# buffer.net
KiCad netlist of a schematic drawn in EAGLE
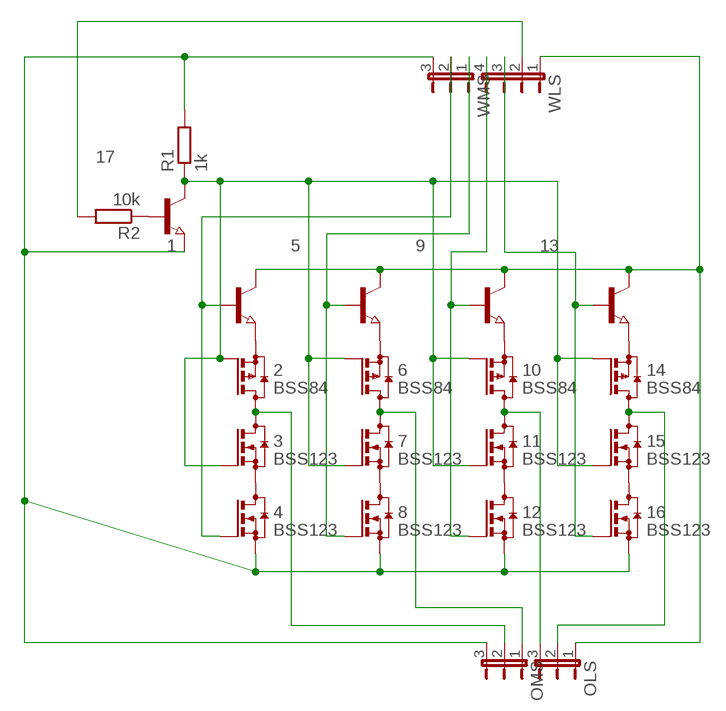
[diagram p0: schematic, sheet 1]

(export (version "E")
  (design (tool "Eeschema 10.0.6"))
  (components
    (comp (ref "1")
      (value "NPN-TRANSISTOR_SOT23")
      (footprint "eagle-import:SOT23")
      (libsource (lib "eagle-import") (part "NPN-TRANSISTOR_SOT23"))
    )
    (comp (ref "2")
      (value "BSS84")
      (footprint "eagle-import:SOT23")
      (libsource (lib "eagle-import") (part "BSS84"))
    )
    (comp (ref "3")
      (value "BSS123")
      (footprint "eagle-import:SOT23")
      (libsource (lib "eagle-import") (part "BSS123"))
    )
    (comp (ref "4")
      (value "BSS123")
      (footprint "eagle-import:SOT23")
      (libsource (lib "eagle-import") (part "BSS123"))
    )
    (comp (ref "5")
      (value "NPN-TRANSISTOR_SOT23")
      (footprint "eagle-import:SOT23")
      (libsource (lib "eagle-import") (part "NPN-TRANSISTOR_SOT23"))
    )
    (comp (ref "6")
      (value "BSS84")
      (footprint "eagle-import:SOT23")
      (libsource (lib "eagle-import") (part "BSS84"))
    )
    (comp (ref "7")
      (value "BSS123")
      (footprint "eagle-import:SOT23")
      (libsource (lib "eagle-import") (part "BSS123"))
    )
    (comp (ref "8")
      (value "BSS123")
      (footprint "eagle-import:SOT23")
      (libsource (lib "eagle-import") (part "BSS123"))
    )
    (comp (ref "9")
      (value "NPN-TRANSISTOR_SOT23")
      (footprint "eagle-import:SOT23")
      (libsource (lib "eagle-import") (part "NPN-TRANSISTOR_SOT23"))
    )
    (comp (ref "10")
      (value "BSS84")
      (footprint "eagle-import:SOT23")
      (libsource (lib "eagle-import") (part "BSS84"))
    )
    (comp (ref "11")
      (value "BSS123")
      (footprint "eagle-import:SOT23")
      (libsource (lib "eagle-import") (part "BSS123"))
    )
    (comp (ref "12")
      (value "BSS123")
      (footprint "eagle-import:SOT23")
      (libsource (lib "eagle-import") (part "BSS123"))
    )
    (comp (ref "13")
      (value "NPN-TRANSISTOR_SOT23")
      (footprint "eagle-import:SOT23")
      (libsource (lib "eagle-import") (part "NPN-TRANSISTOR_SOT23"))
    )
    (comp (ref "14")
      (value "BSS84")
      (footprint "eagle-import:SOT23")
      (libsource (lib "eagle-import") (part "BSS84"))
    )
    (comp (ref "15")
      (value "BSS123")
      (footprint "eagle-import:SOT23")
      (libsource (lib "eagle-import") (part "BSS123"))
    )
    (comp (ref "16")
      (value "BSS123")
      (footprint "eagle-import:SOT23")
      (libsource (lib "eagle-import") (part "BSS123"))
    )
    (comp (ref "17")
      (value "NPN-TRANSISTOR_SOT23")
      (footprint "eagle-import:SOT23")
      (libsource (lib "eagle-import") (part "NPN-TRANSISTOR_SOT23"))
    )
    (comp (ref "OLS")
      (value "JP2E")
      (footprint "eagle-import:JP2")
      (libsource (lib "eagle-import") (part "JP2E"))
    )
    (comp (ref "OMS")
      (value "JP2E")
      (footprint "eagle-import:JP2")
      (libsource (lib "eagle-import") (part "JP2E"))
    )
    (comp (ref "R1")
      (value "1k")
      (footprint "eagle-import:R1206")
      (libsource (lib "eagle-import") (part "R-EU_R1206"))
    )
    (comp (ref "R2")
      (value "10k")
      (footprint "eagle-import:R1206")
      (libsource (lib "eagle-import") (part "R-EU_R1206"))
    )
    (comp (ref "WLS")
      (value "JP4E")
      (footprint "eagle-import:JP4")
      (libsource (lib "eagle-import") (part "JP4E"))
    )
    (comp (ref "WMS")
      (value "JP2E")
      (footprint "eagle-import:JP2")
      (libsource (lib "eagle-import") (part "JP2E"))
    )
  )
  (nets
    (net (code "1") (name "Net-(1-B)") (class "Default")
      (node (ref "1") (pin "1") (pinfunction "B_1") (pintype "passive"))
      (node (ref "4") (pin "1") (pinfunction "G_1") (pintype "passive"))
      (node (ref "WMS") (pin "2") (pinfunction "2_2") (pintype "passive"))
    )
    (net (code "2") (name "Net-(1-C)") (class "Default")
      (node (ref "1") (pin "3") (pinfunction "C_3") (pintype "passive"))
      (node (ref "13") (pin "3") (pinfunction "C_3") (pintype "passive"))
      (node (ref "5") (pin "3") (pinfunction "C_3") (pintype "passive"))
      (node (ref "9") (pin "3") (pinfunction "C_3") (pintype "passive"))
      (node (ref "OLS") (pin "1") (pinfunction "1_1") (pintype "passive"))
      (node (ref "WLS") (pin "1") (pinfunction "1_1") (pintype "passive"))
    )
    (net (code "3") (name "Net-(1-E)") (class "Default")
      (node (ref "1") (pin "2") (pinfunction "E_2") (pintype "passive"))
      (node (ref "2") (pin "2") (pinfunction "S_2") (pintype "passive"))
    )
    (net (code "4") (name "Net-(2-D)") (class "Default")
      (node (ref "2") (pin "3") (pinfunction "D_3") (pintype "passive"))
      (node (ref "3") (pin "3") (pinfunction "D_3") (pintype "passive"))
      (node (ref "OMS") (pin "2") (pinfunction "2_2") (pintype "passive"))
    )
    (net (code "5") (name "Net-(3-S)") (class "Default")
      (node (ref "3") (pin "2") (pinfunction "S_2") (pintype "passive"))
      (node (ref "4") (pin "3") (pinfunction "D_3") (pintype "passive"))
    )
    (net (code "6") (name "Net-(5-B)") (class "Default")
      (node (ref "5") (pin "1") (pinfunction "B_1") (pintype "passive"))
      (node (ref "8") (pin "1") (pinfunction "G_1") (pintype "passive"))
      (node (ref "WMS") (pin "1") (pinfunction "1_1") (pintype "passive"))
    )
    (net (code "7") (name "Net-(5-E)") (class "Default")
      (node (ref "5") (pin "2") (pinfunction "E_2") (pintype "passive"))
      (node (ref "6") (pin "2") (pinfunction "S_2") (pintype "passive"))
    )
    (net (code "8") (name "Net-(6-D)") (class "Default")
      (node (ref "6") (pin "3") (pinfunction "D_3") (pintype "passive"))
      (node (ref "7") (pin "3") (pinfunction "D_3") (pintype "passive"))
      (node (ref "OMS") (pin "1") (pinfunction "1_1") (pintype "passive"))
    )
    (net (code "9") (name "Net-(7-S)") (class "Default")
      (node (ref "7") (pin "2") (pinfunction "S_2") (pintype "passive"))
      (node (ref "8") (pin "3") (pinfunction "D_3") (pintype "passive"))
    )
    (net (code "10") (name "Net-(10-D)") (class "Default")
      (node (ref "10") (pin "3") (pinfunction "D_3") (pintype "passive"))
      (node (ref "11") (pin "3") (pinfunction "D_3") (pintype "passive"))
      (node (ref "OLS") (pin "3") (pinfunction "3_3") (pintype "passive"))
    )
    (net (code "11") (name "Net-(10-G)") (class "Default")
      (node (ref "10") (pin "1") (pinfunction "G_1") (pintype "passive"))
      (node (ref "11") (pin "1") (pinfunction "G_1") (pintype "passive"))
      (node (ref "14") (pin "1") (pinfunction "G_1") (pintype "passive"))
      (node (ref "15") (pin "1") (pinfunction "G_1") (pintype "passive"))
      (node (ref "17") (pin "3") (pinfunction "C_3") (pintype "passive"))
      (node (ref "2") (pin "1") (pinfunction "G_1") (pintype "passive"))
      (node (ref "3") (pin "1") (pinfunction "G_1") (pintype "passive"))
      (node (ref "6") (pin "1") (pinfunction "G_1") (pintype "passive"))
      (node (ref "7") (pin "1") (pinfunction "G_1") (pintype "passive"))
      (node (ref "R1") (pin "1") (pinfunction "1_1") (pintype "passive"))
    )
    (net (code "12") (name "Net-(10-S)") (class "Default")
      (node (ref "10") (pin "2") (pinfunction "S_2") (pintype "passive"))
      (node (ref "9") (pin "2") (pinfunction "E_2") (pintype "passive"))
    )
    (net (code "13") (name "Net-(11-S)") (class "Default")
      (node (ref "11") (pin "2") (pinfunction "S_2") (pintype "passive"))
      (node (ref "12") (pin "3") (pinfunction "D_3") (pintype "passive"))
    )
    (net (code "14") (name "Net-(12-G)") (class "Default")
      (node (ref "12") (pin "1") (pinfunction "G_1") (pintype "passive"))
      (node (ref "9") (pin "1") (pinfunction "B_1") (pintype "passive"))
      (node (ref "WLS") (pin "4") (pinfunction "4_4") (pintype "passive"))
    )
    (net (code "15") (name "Net-(12-S)") (class "Default")
      (node (ref "12") (pin "2") (pinfunction "S_2") (pintype "passive"))
      (node (ref "16") (pin "2") (pinfunction "S_2") (pintype "passive"))
      (node (ref "17") (pin "2") (pinfunction "E_2") (pintype "passive"))
      (node (ref "4") (pin "2") (pinfunction "S_2") (pintype "passive"))
      (node (ref "8") (pin "2") (pinfunction "S_2") (pintype "passive"))
      (node (ref "OMS") (pin "3") (pinfunction "3_3") (pintype "passive"))
      (node (ref "R1") (pin "2") (pinfunction "2_2") (pintype "passive"))
      (node (ref "WMS") (pin "3") (pinfunction "3_3") (pintype "passive"))
    )
    (net (code "16") (name "Net-(13-B)") (class "Default")
      (node (ref "13") (pin "1") (pinfunction "B_1") (pintype "passive"))
      (node (ref "16") (pin "1") (pinfunction "G_1") (pintype "passive"))
      (node (ref "WLS") (pin "3") (pinfunction "3_3") (pintype "passive"))
    )
    (net (code "17") (name "Net-(13-E)") (class "Default")
      (node (ref "13") (pin "2") (pinfunction "E_2") (pintype "passive"))
      (node (ref "14") (pin "2") (pinfunction "S_2") (pintype "passive"))
    )
    (net (code "18") (name "Net-(14-D)") (class "Default")
      (node (ref "14") (pin "3") (pinfunction "D_3") (pintype "passive"))
      (node (ref "15") (pin "3") (pinfunction "D_3") (pintype "passive"))
      (node (ref "OLS") (pin "2") (pinfunction "2_2") (pintype "passive"))
    )
    (net (code "19") (name "Net-(15-S)") (class "Default")
      (node (ref "15") (pin "2") (pinfunction "S_2") (pintype "passive"))
      (node (ref "16") (pin "3") (pinfunction "D_3") (pintype "passive"))
    )
    (net (code "20") (name "Net-(17-B)") (class "Default")
      (node (ref "17") (pin "1") (pinfunction "B_1") (pintype "passive"))
      (node (ref "R2") (pin "1") (pinfunction "1_1") (pintype "passive"))
    )
    (net (code "21") (name "Net-(R2-Pad2)") (class "Default")
      (node (ref "R2") (pin "2") (pinfunction "2_2") (pintype "passive"))
      (node (ref "WLS") (pin "2") (pinfunction "2_2") (pintype "passive"))
    )
  )
)
